# Communication.net
KiCad netlist of a schematic drawn in Altium Designer
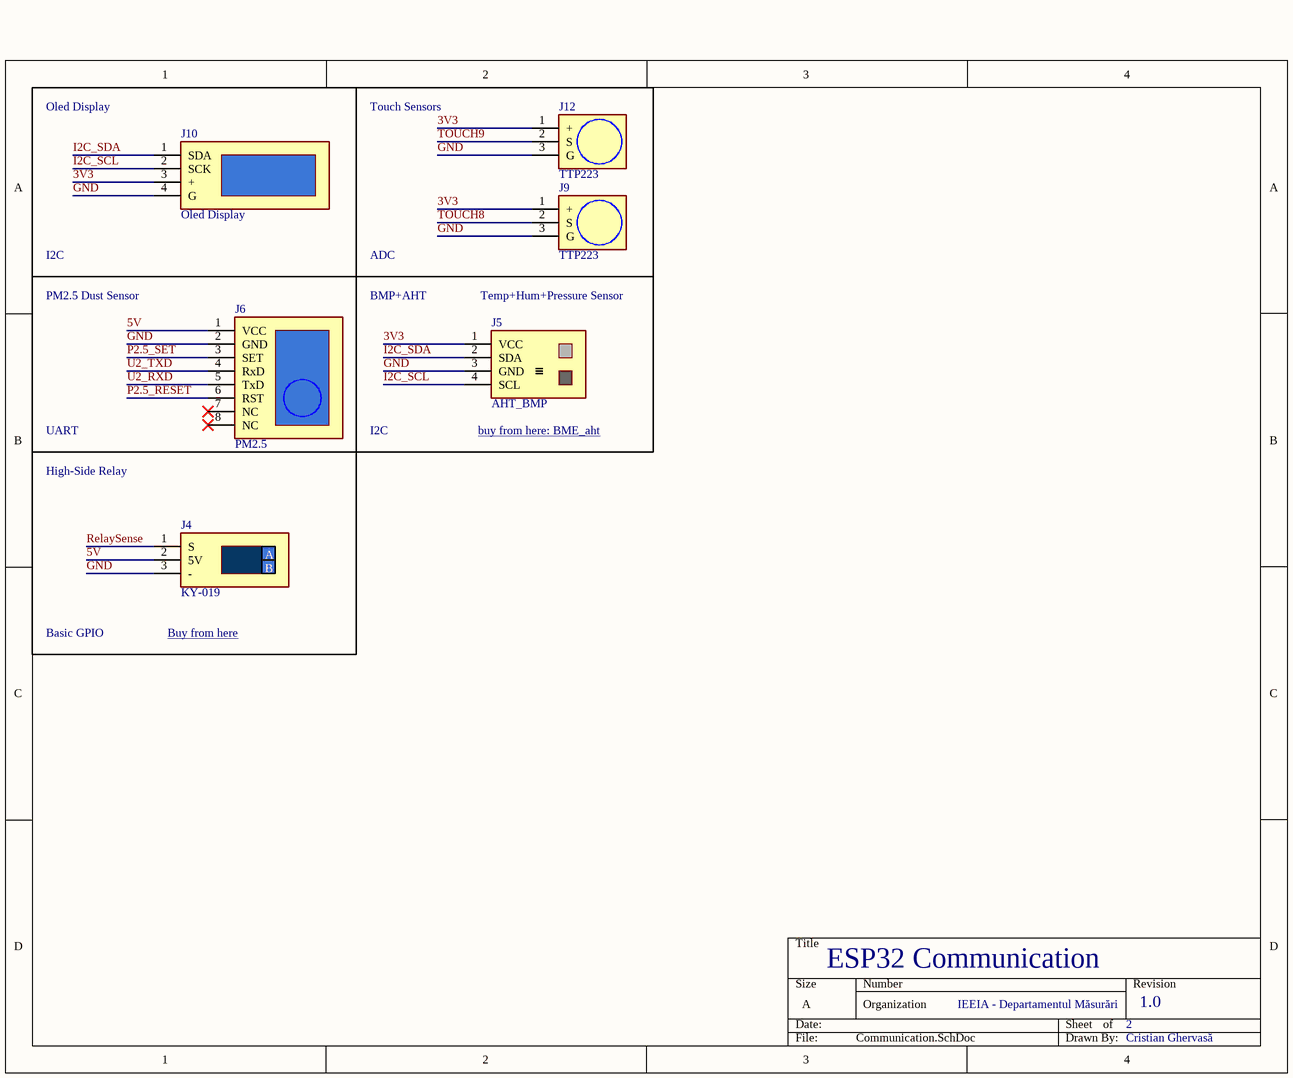
[diagram p0: Communication.SchDoc]

(export (version "E")
  (design (tool "Eeschema 10.0.6"))
  (components
    (comp (ref "J4")
      (value "KY-019")
      (footprint "KY-019")
      (description "High-Side Relay")
      (libsource (lib "My_Forecaster") (part "KY-019"))
    )
    (comp (ref "J5")
      (value "AHT_BMP")
      (footprint "BMP280_AHT20")
      (description "BMP280+AHT20. Temp+Humidity+Pressure.")
      (libsource (lib "My_Forecaster") (part "AHT_BMP"))
    )
    (comp (ref "J6")
      (value "PM2.5")
      (footprint "PM2.5")
      (description "Dust Sensor")
      (libsource (lib "My_Forecaster") (part "PM2.5"))
    )
    (comp (ref "J9")
      (value "TTP223")
      (footprint "TTP223_Sensor")
      (description "Touch Sensor")
      (libsource (lib "My_Forecaster") (part "TTP223"))
    )
    (comp (ref "J10")
      (value "Oled Display")
      (footprint "OLED_0.91_128x32")
      (libsource (lib "My_Forecaster") (part "OLED_0.91_128x32"))
    )
    (comp (ref "J12")
      (value "TTP223")
      (footprint "TTP223_Sensor")
      (description "Touch Sensor")
      (libsource (lib "My_Forecaster") (part "TTP223"))
    )
  )
  (nets
    (net (code "1") (name "/3V3") (class "Default")
      (node (ref "J10") (pin "3") (pinfunction "+_3") (pintype "passive"))
      (node (ref "J12") (pin "1") (pinfunction "+_1") (pintype "passive"))
      (node (ref "J5") (pin "1") (pinfunction "VCC_1") (pintype "passive"))
      (node (ref "J9") (pin "1") (pinfunction "+_1") (pintype "passive"))
    )
    (net (code "2") (name "/5V") (class "Default")
      (node (ref "J4") (pin "2") (pinfunction "5V_2") (pintype "passive"))
      (node (ref "J6") (pin "1") (pinfunction "VCC_1") (pintype "passive"))
    )
    (net (code "3") (name "/GND") (class "Default")
      (node (ref "J10") (pin "4") (pinfunction "G_4") (pintype "passive"))
      (node (ref "J12") (pin "3") (pinfunction "G_3") (pintype "passive"))
      (node (ref "J4") (pin "3") (pinfunction "-_3") (pintype "passive"))
      (node (ref "J5") (pin "3") (pinfunction "GND_3") (pintype "passive"))
      (node (ref "J6") (pin "2") (pinfunction "GND_2") (pintype "passive"))
      (node (ref "J9") (pin "3") (pinfunction "G_3") (pintype "passive"))
    )
    (net (code "4") (name "/I2C_SCL") (class "Default")
      (node (ref "J10") (pin "2") (pinfunction "SCK_2") (pintype "passive"))
      (node (ref "J5") (pin "4") (pinfunction "SCL_4") (pintype "passive"))
    )
    (net (code "5") (name "/I2C_SDA") (class "Default")
      (node (ref "J10") (pin "1") (pinfunction "SDA_1") (pintype "passive"))
      (node (ref "J5") (pin "2") (pinfunction "SDA_2") (pintype "passive"))
    )
    (net (code "6") (name "/P2.5_RESET") (class "Default")
      (node (ref "J6") (pin "6") (pinfunction "RST_6") (pintype "passive"))
    )
    (net (code "7") (name "/P2.5_SET") (class "Default")
      (node (ref "J6") (pin "3") (pinfunction "SET_3") (pintype "passive"))
    )
    (net (code "8") (name "/RelaySense") (class "Default")
      (node (ref "J4") (pin "1") (pinfunction "S_1") (pintype "passive"))
    )
    (net (code "9") (name "/TOUCH8") (class "Default")
      (node (ref "J9") (pin "2") (pinfunction "S_2") (pintype "passive"))
    )
    (net (code "10") (name "/TOUCH9") (class "Default")
      (node (ref "J12") (pin "2") (pinfunction "S_2") (pintype "passive"))
    )
    (net (code "11") (name "/U2_RXD") (class "Default")
      (node (ref "J6") (pin "5") (pinfunction "TxD_5") (pintype "passive"))
    )
    (net (code "12") (name "/U2_TXD") (class "Default")
      (node (ref "J6") (pin "4") (pinfunction "RxD_4") (pintype "passive"))
    )
    (net (code "13") (name "unconnected-(J6-NC-Pad7)") (class "Default")
      (node (ref "J6") (pin "7") (pinfunction "NC_7") (pintype "passive+no_connect"))
    )
    (net (code "14") (name "unconnected-(J6-NC-Pad8)") (class "Default")
      (node (ref "J6") (pin "8") (pinfunction "NC_8") (pintype "passive+no_connect"))
    )
  )
)
